# Adafruit_INA169_CurPowerMonitor.net
KiCad netlist of a schematic drawn in EAGLE
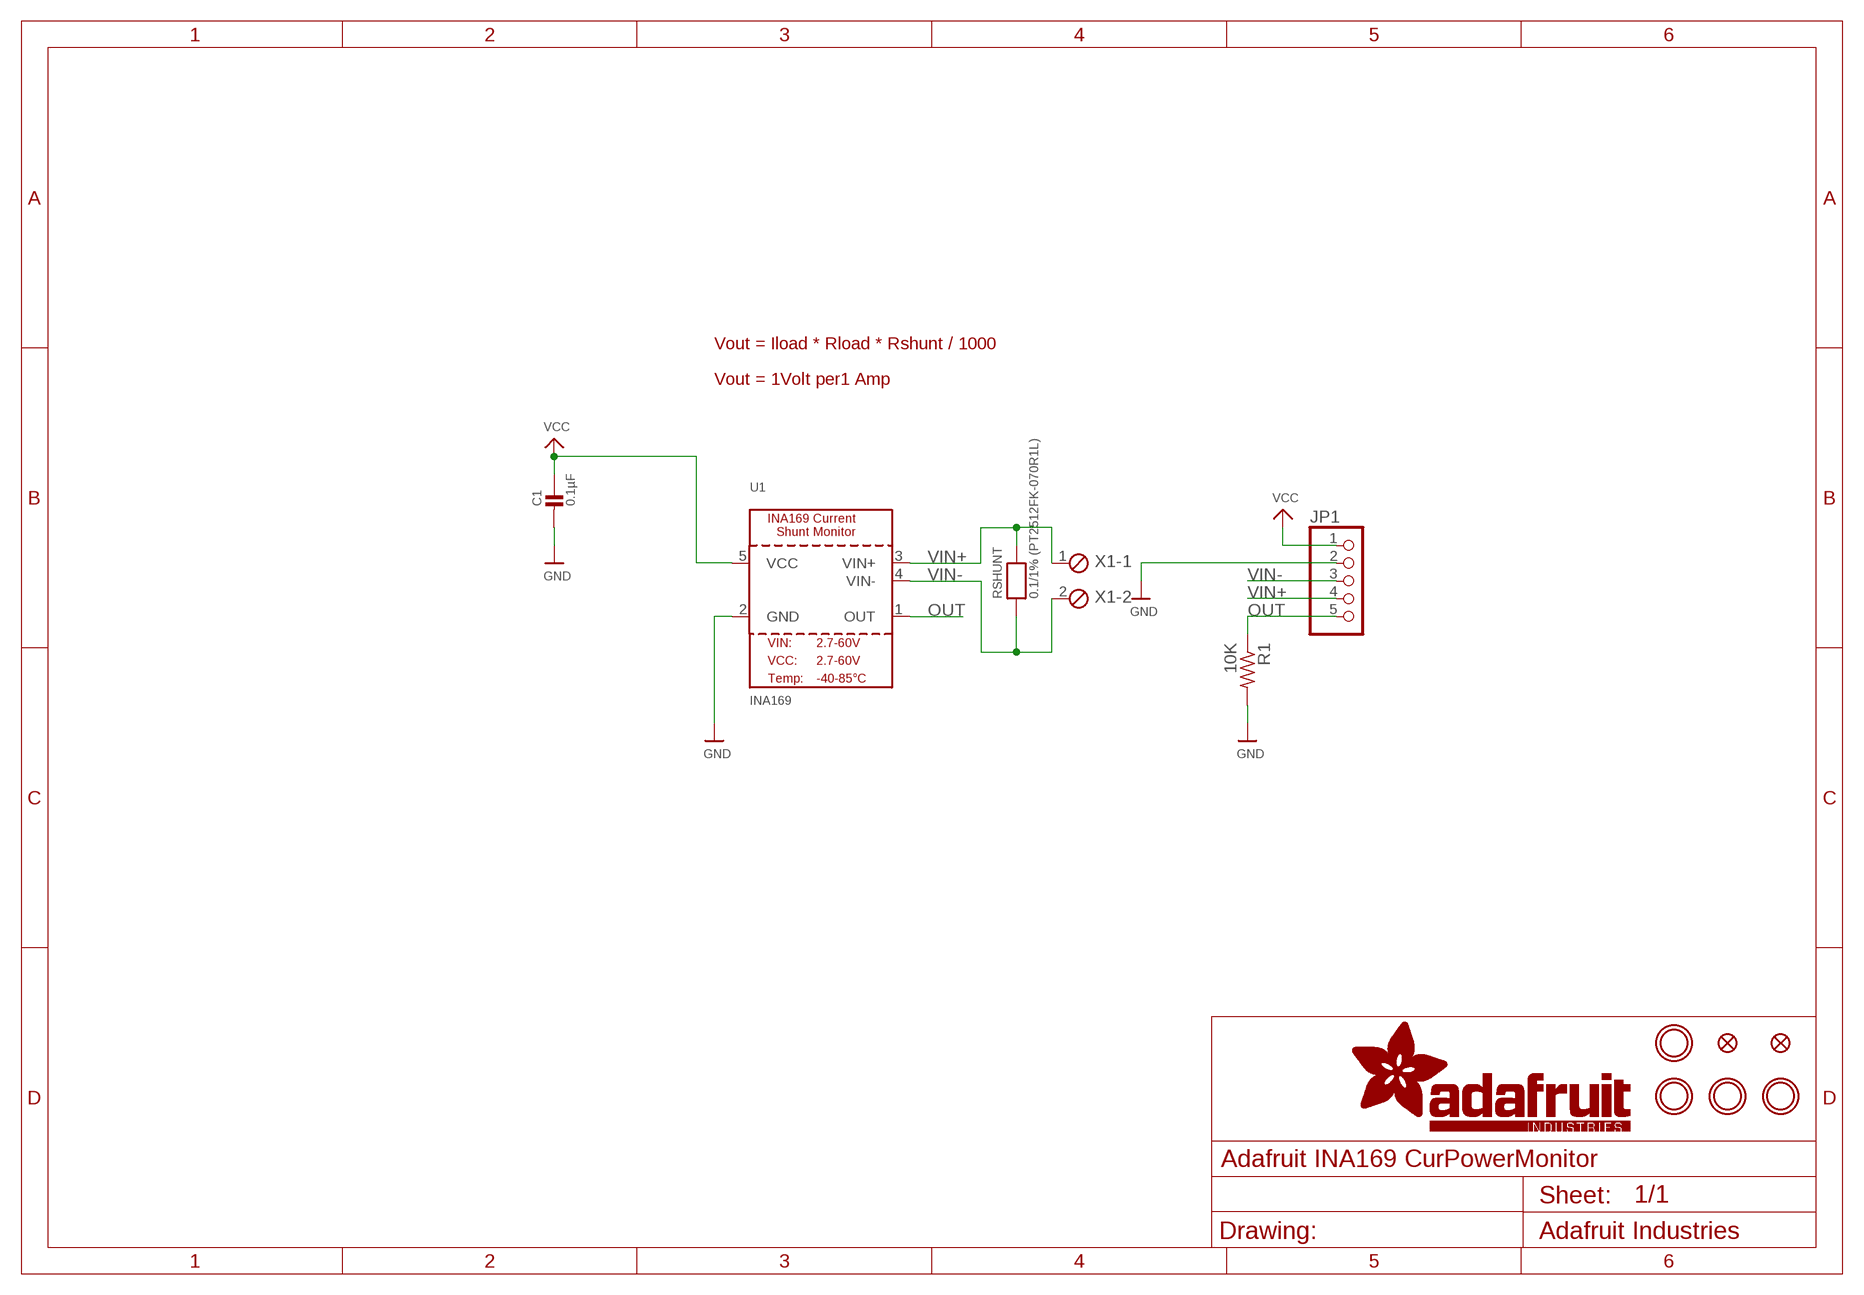
[diagram p0: schematic, sheet 1]

(export (version "E")
  (design (tool "Eeschema 10.0.6"))
  (components
    (comp (ref "C1")
      (value "0.1µF")
      (footprint "eagle-import:0805")
      (libsource (lib "eagle-import") (part "CAP_CERAMIC0805"))
    )
    (comp (ref "FID1")
      (value "FIDUCIAL\"\"")
      (footprint "eagle-import:FIDUCIAL_1MM")
      (libsource (lib "eagle-import") (part "FIDUCIAL{dblquote}{dblquote}"))
    )
    (comp (ref "FID2")
      (value "FIDUCIAL\"\"")
      (footprint "eagle-import:FIDUCIAL_1MM")
      (libsource (lib "eagle-import") (part "FIDUCIAL{dblquote}{dblquote}"))
    )
    (comp (ref "JP1")
      (value "HEADER-1X570MIL")
      (footprint "eagle-import:1X05_ROUND_70")
      (libsource (lib "eagle-import") (part "HEADER-1X570MIL"))
    )
    (comp (ref "R1")
      (value "10K")
      (footprint "eagle-import:0805-THM")
      (libsource (lib "eagle-import") (part "RESISTOR_DUAL"))
    )
    (comp (ref "RSHUNT")
      (value "0.1/1% (PT2512FK-070R1L)")
      (footprint "eagle-import:2512")
      (libsource (lib "eagle-import") (part "RESISTOR2512"))
    )
    (comp (ref "U$7")
      (value "MOUNTINGHOLE2.5")
      (footprint "eagle-import:MOUNTINGHOLE_2.5_PLATED")
      (libsource (lib "eagle-import") (part "MOUNTINGHOLE2.5"))
    )
    (comp (ref "U$8")
      (value "MOUNTINGHOLE2.5")
      (footprint "eagle-import:MOUNTINGHOLE_2.5_PLATED")
      (libsource (lib "eagle-import") (part "MOUNTINGHOLE2.5"))
    )
    (comp (ref "U$9")
      (value "MOUNTINGHOLE2.5")
      (footprint "eagle-import:MOUNTINGHOLE_2.5_PLATED")
      (libsource (lib "eagle-import") (part "MOUNTINGHOLE2.5"))
    )
    (comp (ref "U$10")
      (value "MOUNTINGHOLE2.5")
      (footprint "eagle-import:MOUNTINGHOLE_2.5_PLATED")
      (libsource (lib "eagle-import") (part "MOUNTINGHOLE2.5"))
    )
    (comp (ref "U1")
      (value "INA169")
      (footprint "eagle-import:SOT23-5")
      (libsource (lib "eagle-import") (part "INA169"))
    )
    (comp (ref "X1")
      (value "MPT2")
      (footprint "eagle-import:2POL254")
      (libsource (lib "eagle-import") (part "MPT2"))
    )
  )
  (nets
    (net (code "1") (name "/OUT") (class "Default")
      (node (ref "JP1") (pin "5") (pinfunction "5_5") (pintype "passive"))
      (node (ref "R1") (pin "1") (pinfunction "1_1") (pintype "passive"))
      (node (ref "U1") (pin "1") (pinfunction "OUT_1") (pintype "output"))
    )
    (net (code "2") (name "/VIN+") (class "Default")
      (node (ref "JP1") (pin "4") (pinfunction "4_4") (pintype "passive"))
      (node (ref "RSHUNT") (pin "2") (pinfunction "2_2") (pintype "passive"))
      (node (ref "U1") (pin "3") (pinfunction "VIN+_3") (pintype "bidirectional"))
      (node (ref "X1") (pin "1") (pinfunction "1_1") (pintype "passive"))
    )
    (net (code "3") (name "/VIN-") (class "Default")
      (node (ref "JP1") (pin "3") (pinfunction "3_3") (pintype "passive"))
      (node (ref "RSHUNT") (pin "1") (pinfunction "1_1") (pintype "passive"))
      (node (ref "U1") (pin "4") (pinfunction "VIN-_4") (pintype "bidirectional"))
      (node (ref "X1") (pin "2") (pinfunction "1_2") (pintype "passive"))
    )
    (net (code "4") (name "GND") (class "Default")
      (node (ref "C1") (pin "2") (pinfunction "2_2") (pintype "passive"))
      (node (ref "JP1") (pin "2") (pinfunction "2_2") (pintype "passive"))
      (node (ref "R1") (pin "2") (pinfunction "2_2") (pintype "passive"))
      (node (ref "U1") (pin "2") (pinfunction "GND_2") (pintype "power_in"))
    )
    (net (code "5") (name "VCC") (class "Default")
      (node (ref "C1") (pin "1") (pinfunction "1_1") (pintype "passive"))
      (node (ref "JP1") (pin "1") (pinfunction "1_1") (pintype "passive"))
      (node (ref "U1") (pin "5") (pinfunction "VCC_5") (pintype "power_in"))
    )
  )
)
